# DB10012_ControlTopLevel.net
KiCad netlist of a schematic drawn in Altium Designer
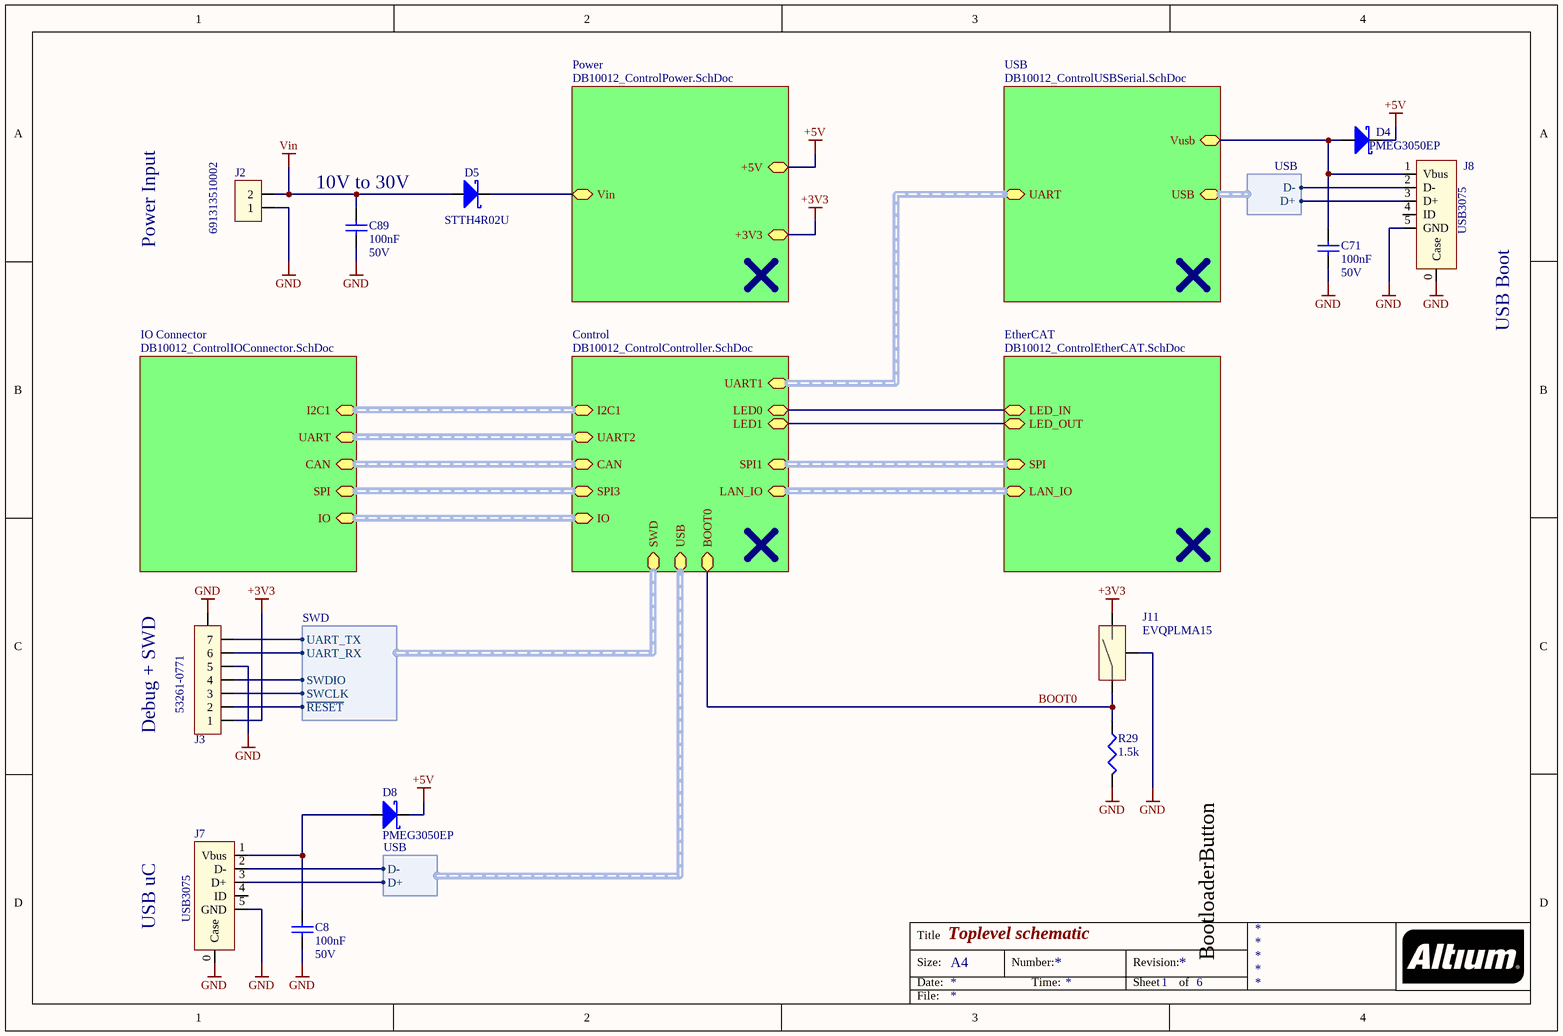
[diagram p0: DB10012_ControlTopLevel.SchDoc]

(export (version "E")
  (design (tool "Eeschema 10.0.6"))
  (components
    (comp (ref "C8")
      (value "100nF")
      (footprint "C-0805")
      (description "Capacitor, 100nF, 50V,  X7R")
      (fields (field (name "VOLTAGE RATING") "50V"))
      (libsource (lib "AR_Capacitors_Ceramic") (part "100nF/0805/CER/50V"))
    )
    (comp (ref "C71")
      (value "100nF")
      (footprint "C-0805")
      (description "Capacitor, 100nF, 50V,  X7R")
      (fields (field (name "VOLTAGE RATING") "50V"))
      (libsource (lib "AR_Capacitors_Ceramic") (part "100nF/0805/CER/50V"))
    )
    (comp (ref "C89")
      (value "100nF")
      (footprint "C-0805")
      (description "Capacitor, 100nF, 50V,  X7R")
      (fields (field (name "VOLTAGE RATING") "50V"))
      (libsource (lib "AR_Capacitors_Ceramic") (part "100nF/0805/CER/50V"))
    )
    (comp (ref "D4")
      (value "PMEG3050EP")
      (footprint "SOD128")
      (description "Diode Schottky, Vrrm: 30V, If: 3A, Vf: 0.36V")
      (libsource (lib "AR_Diodes") (part "PMEG3050EP"))
    )
    (comp (ref "D5")
      (value "STTH4R02U")
      (footprint "CASE 403A-03")
      (description "Diode Schottky, Vrrm: 200V, If: 4A, Vf: 1,05V")
      (libsource (lib "AR_Diodes") (part "STTH4R02U"))
    )
    (comp (ref "D8")
      (value "PMEG3050EP")
      (footprint "SOD128")
      (description "Diode Schottky, Vrrm: 30V, If: 3A, Vf: 0.36V")
      (libsource (lib "AR_Diodes") (part "PMEG3050EP"))
    )
    (comp (ref "J2")
      (value "691313510002")
      (footprint "691313510002")
      (description "WR-TBL 313 Series, 2 Contacts, Header, 5.08 mm")
      (libsource (lib "AR_Connectors") (part "691313510002"))
    )
    (comp (ref "J3")
      (value "53261-0771")
      (footprint "53261-0771")
      (description "PicoBlade 53261 Series, 7Pin, Right Angle")
      (libsource (lib "AR_Connectors") (part "53261-0771"))
    )
    (comp (ref "J7")
      (value "USB3075")
      (footprint "USB3075 - NOSLOT")
      (description "USB 2.0 MICRO B, RCPT, 5POS, SMT")
      (libsource (lib "AR_Connectors") (part "USB3075"))
    )
    (comp (ref "J8")
      (value "USB3075")
      (footprint "USB3075 - NOSLOT")
      (description "USB 2.0 MICRO B, RCPT, 5POS, SMT")
      (libsource (lib "") (part "USB3075_1"))
    )
    (comp (ref "J11")
      (value "EVQPLMA15")
      (footprint "EVQPLM")
      (description "SWITCH, TACT, 4.9MM, SMD, 2.6N")
      (libsource (lib "AR_Misc") (part "EVQPLMA15"))
    )
    (comp (ref "R29")
      (value "1.5k")
      (footprint "0402")
      (description "Resistor, 1.5k, 0.1%, 0.0625W, 50V, 100PPM, 0402")
      (libsource (lib "AR_Resistors_SMD") (part "1.5k/0402/0063W/50V"))
    )
  )
  (nets
    (net (code "3") (name "+3V3") (class "Default")
      (node (ref "J11") (pin "2") (pinfunction "2_2") (pintype "passive"))
      (node (ref "J3") (pin "1") (pinfunction "1_1") (pintype "passive"))
    )
    (net (code "4") (name "+5V") (class "Default")
      (node (ref "D4") (pin "2") (pinfunction "K_2") (pintype "passive"))
      (node (ref "D8") (pin "2") (pinfunction "K_2") (pintype "passive"))
    )
    (net (code "5") (name "/BOOT0") (class "Default")
      (node (ref "J11") (pin "1") (pinfunction "1_1") (pintype "passive"))
      (node (ref "R29") (pin "2") (pinfunction "2_2") (pintype "passive"))
    )
    (net (code "14") (name "/SWCLK") (class "Default")
      (node (ref "J3") (pin "3") (pinfunction "3_3") (pintype "passive"))
    )
    (net (code "15") (name "/SWDIO") (class "Default")
      (node (ref "J3") (pin "4") (pinfunction "4_4") (pintype "passive"))
    )
    (net (code "18") (name "/UART_RX") (class "Default")
      (node (ref "J3") (pin "6") (pinfunction "6_6") (pintype "passive"))
    )
    (net (code "19") (name "/UART_TX") (class "Default")
      (node (ref "J3") (pin "7") (pinfunction "7_7") (pintype "passive"))
    )
    (net (code "20") (name "/Vin") (class "Default")
      (node (ref "D5") (pin "2") (pinfunction "K_2") (pintype "passive"))
    )
    (net (code "21") (name "/Vusb") (class "Default")
      (node (ref "C71") (pin "2") (pinfunction "2_2") (pintype "passive"))
      (node (ref "D4") (pin "1") (pinfunction "A_1") (pintype "passive"))
      (node (ref "J8") (pin "1") (pinfunction "Vbus_1") (pintype "passive"))
    )
    (net (code "24") (name "/~{RESET}") (class "Default")
      (node (ref "J3") (pin "2") (pinfunction "2_2") (pintype "passive"))
    )
    (net (code "25") (name "GND") (class "Default")
      (node (ref "C71") (pin "1") (pinfunction "1_1") (pintype "passive"))
      (node (ref "C8") (pin "1") (pinfunction "1_1") (pintype "passive"))
      (node (ref "C89") (pin "1") (pinfunction "1_1") (pintype "passive"))
      (node (ref "J11") (pin "0") (pinfunction "GND_0") (pintype "passive"))
      (node (ref "J2") (pin "1") (pinfunction "1_1") (pintype "passive"))
      (node (ref "J3") (pin "0") (pinfunction "SHLD_0") (pintype "passive"))
      (node (ref "J3") (pin "5") (pinfunction "5_5") (pintype "passive"))
      (node (ref "J7") (pin "0") (pinfunction "Case_0") (pintype "passive"))
      (node (ref "J7") (pin "5") (pinfunction "GND_5") (pintype "passive"))
      (node (ref "J8") (pin "0") (pinfunction "Case_0") (pintype "passive"))
      (node (ref "J8") (pin "5") (pinfunction "GND_5") (pintype "passive"))
      (node (ref "R29") (pin "1") (pinfunction "1_1") (pintype "passive"))
    )
    (net (code "26") (name "Net-(D8-A)") (class "Default")
      (node (ref "C8") (pin "2") (pinfunction "2_2") (pintype "passive"))
      (node (ref "D8") (pin "1") (pinfunction "A_1") (pintype "passive"))
      (node (ref "J7") (pin "1") (pinfunction "Vbus_1") (pintype "passive"))
    )
    (net (code "27") (name "Vin") (class "Default")
      (node (ref "C89") (pin "2") (pinfunction "2_2") (pintype "passive"))
      (node (ref "D5") (pin "1") (pinfunction "A_1") (pintype "passive"))
      (node (ref "J2") (pin "2") (pinfunction "2_2") (pintype "passive"))
    )
    (net (code "28") (name "unconnected-(J7-D+-Pad3)") (class "Default")
      (node (ref "J7") (pin "3") (pinfunction "D+_3") (pintype "passive"))
    )
    (net (code "29") (name "unconnected-(J7-D--Pad2)") (class "Default")
      (node (ref "J7") (pin "2") (pinfunction "D-_2") (pintype "passive"))
    )
    (net (code "30") (name "unconnected-(J7-ID-Pad4)") (class "Default")
      (node (ref "J7") (pin "4") (pinfunction "ID_4") (pintype "passive"))
    )
    (net (code "31") (name "unconnected-(J8-D+-Pad3)") (class "Default")
      (node (ref "J8") (pin "3") (pinfunction "D+_3") (pintype "passive"))
    )
    (net (code "32") (name "unconnected-(J8-D--Pad2)") (class "Default")
      (node (ref "J8") (pin "2") (pinfunction "D-_2") (pintype "passive"))
    )
    (net (code "33") (name "unconnected-(J8-ID-Pad4)") (class "Default")
      (node (ref "J8") (pin "4") (pinfunction "ID_4") (pintype "passive"))
    )
  )
)
